# LED_Sch.net
KiCad netlist of a schematic drawn in Altium Designer
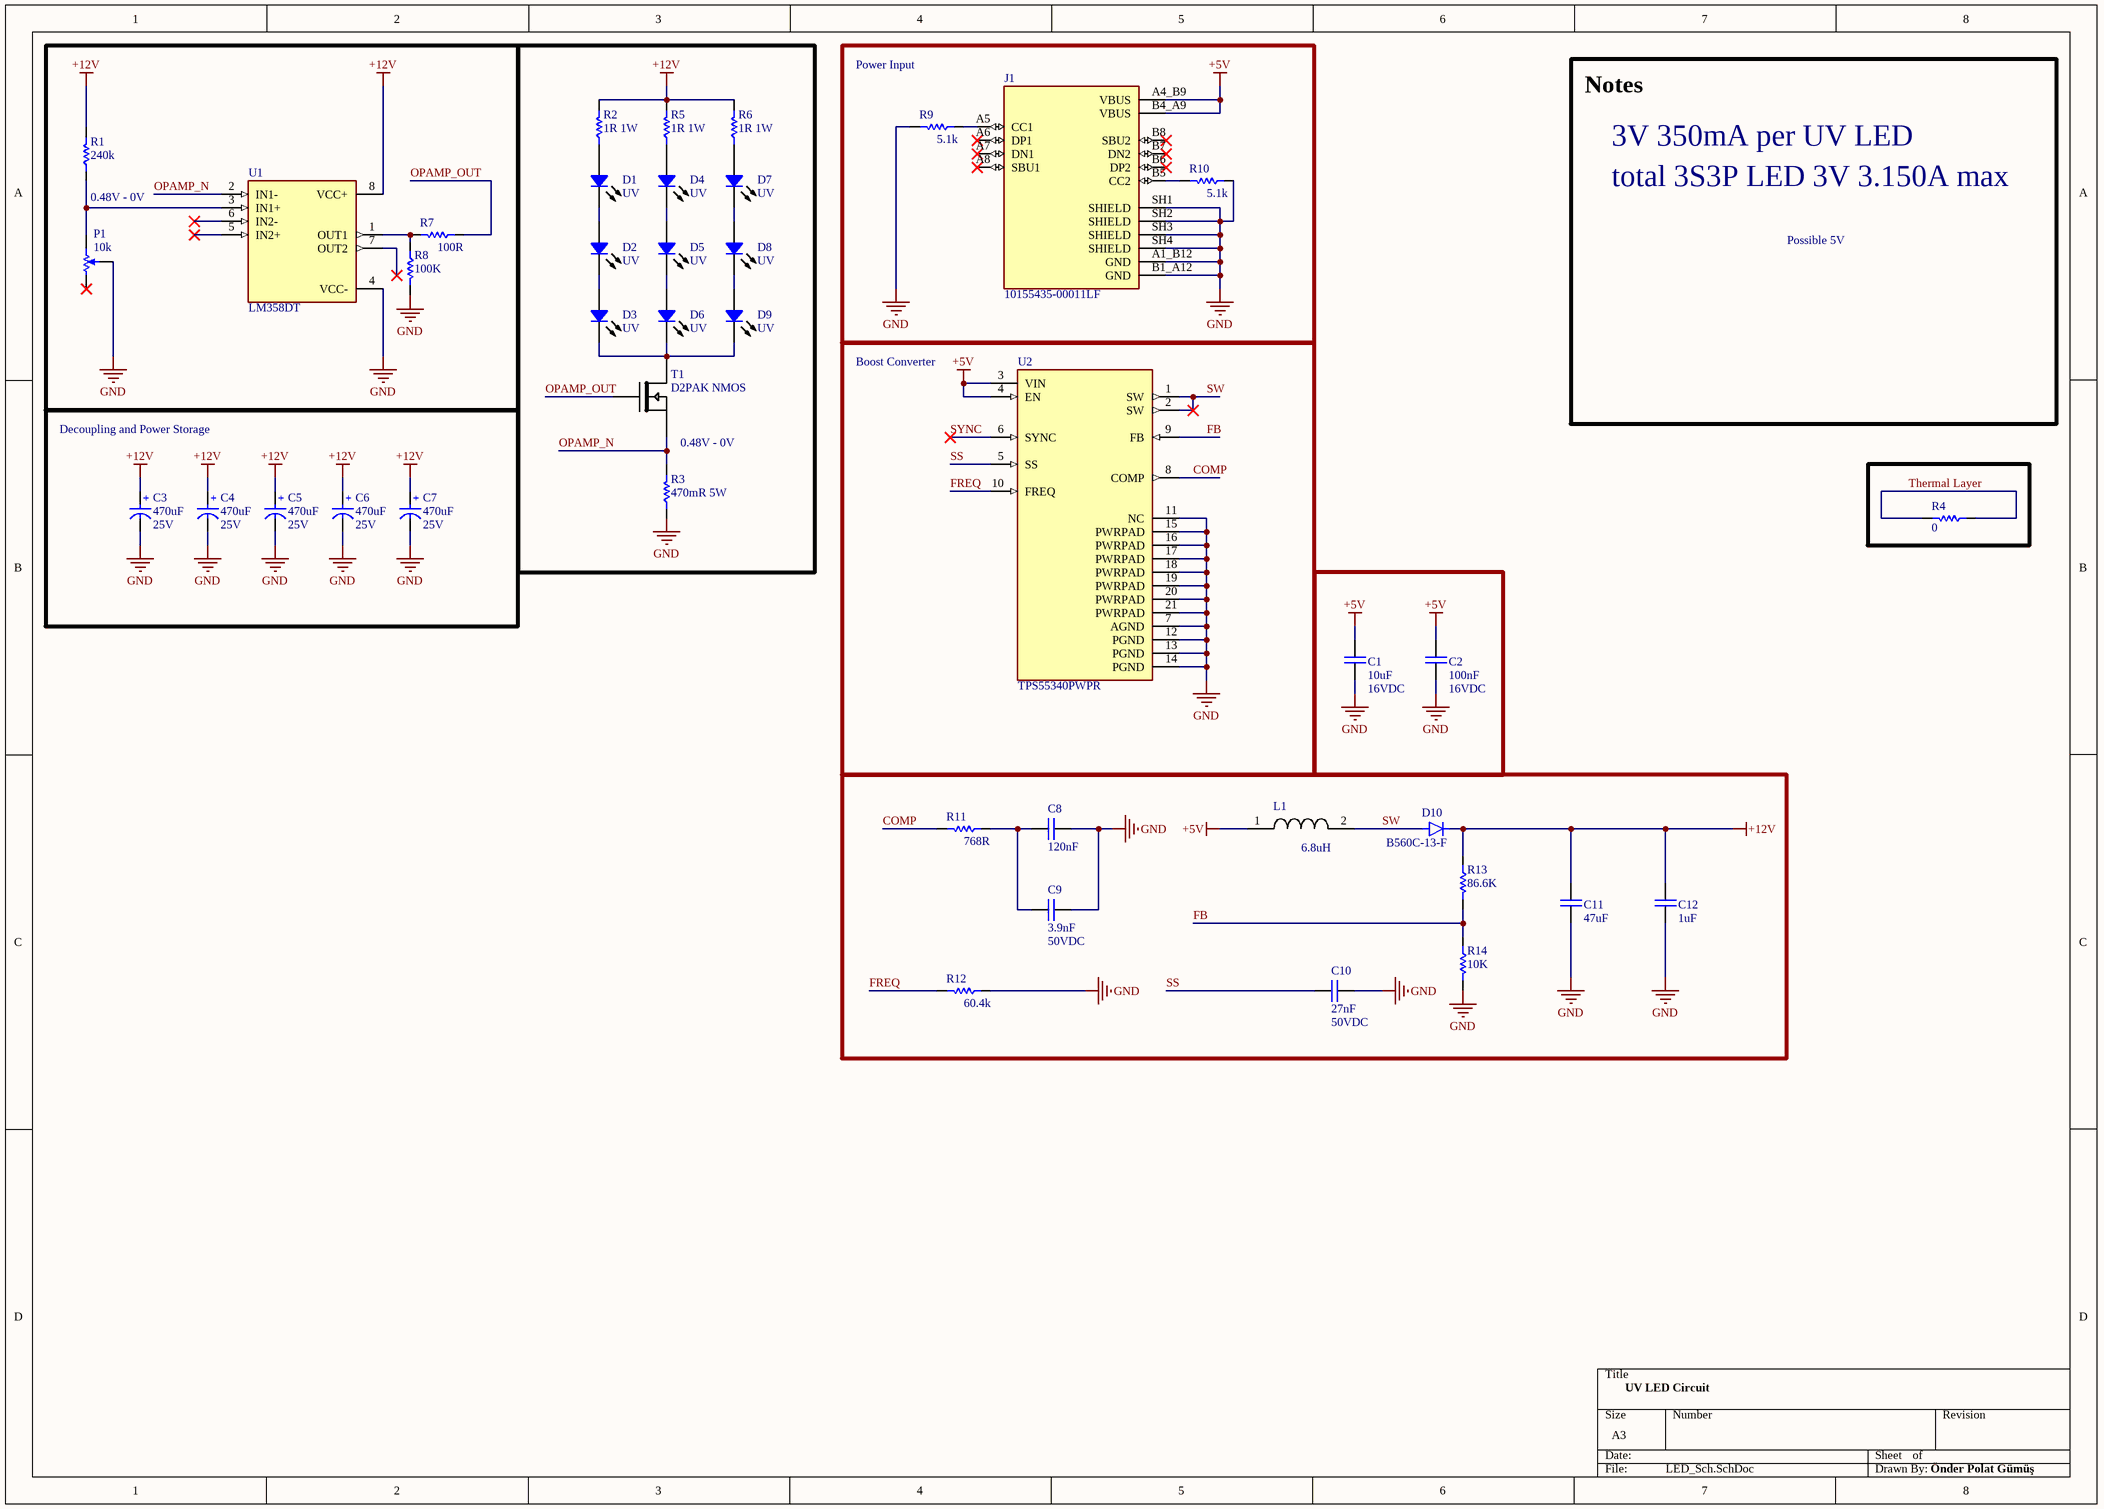
[diagram p0: LED_Sch.SchDoc]

(export (version "E")
  (design (tool "Eeschema 10.0.6"))
  (components
    (comp (ref "C1")
      (value "10uF")
      (footprint "CAP 1206/3216")
      (description "Bipolar ceramic capacitor SMD")
      (fields (field (name "RATING") "16VDC") (field (name "VALIDATION") "Valid"))
      (libsource (lib "aKaReZa") (part "Cap_Multi_SMD"))
    )
    (comp (ref "C2")
      (value "100nF")
      (footprint "CAP 1206/3216")
      (description "Bipolar ceramic capacitor SMD")
      (fields (field (name "RATING") "16VDC") (field (name "VALIDATION") "Valid"))
      (libsource (lib "aKaReZa") (part "Cap_Multi_SMD"))
    )
    (comp (ref "C3")
      (value "470uF")
      (footprint "cap 03")
      (description "Electrolit Capacitor")
      (fields (field (name "RATING") "25V") (field (name "VALIDATION") "Valid"))
      (libsource (lib "aKaReZa") (part "Cap_Electrolit"))
    )
    (comp (ref "C4")
      (value "470uF")
      (footprint "cap 03")
      (description "Electrolit Capacitor")
      (fields (field (name "RATING") "25V") (field (name "VALIDATION") "Valid"))
      (libsource (lib "aKaReZa") (part "Cap_Electrolit"))
    )
    (comp (ref "C5")
      (value "470uF")
      (footprint "cap 03")
      (description "Electrolit Capacitor")
      (fields (field (name "RATING") "25V") (field (name "VALIDATION") "Valid"))
      (libsource (lib "aKaReZa") (part "Cap_Electrolit"))
    )
    (comp (ref "C6")
      (value "470uF")
      (footprint "cap 03")
      (description "Electrolit Capacitor")
      (fields (field (name "RATING") "25V") (field (name "VALIDATION") "Valid"))
      (libsource (lib "aKaReZa") (part "Cap_Electrolit"))
    )
    (comp (ref "C7")
      (value "470uF")
      (footprint "cap 03")
      (description "Electrolit Capacitor")
      (fields (field (name "RATING") "25V") (field (name "VALIDATION") "Valid"))
      (libsource (lib "aKaReZa") (part "Cap_Electrolit"))
    )
    (comp (ref "C8")
      (value "120nF")
      (footprint "1812_C")
      (description "Bipolar ceramic capacitor SMD")
      (fields (field (name "VALIDATION") "Valid"))
      (libsource (lib "aKaReZa") (part "Cap_Multi_SMD"))
    )
    (comp (ref "C9")
      (value "3.9nF")
      (footprint "CAP 0603/1608")
      (description "Bipolar ceramic capacitor SMD")
      (fields (field (name "RATING") "50VDC") (field (name "VALIDATION") "Valid"))
      (libsource (lib "aKaReZa") (part "Cap_Multi_SMD"))
    )
    (comp (ref "C10")
      (value "27nF")
      (footprint "CAP 0805/2012")
      (description "Bipolar ceramic capacitor SMD")
      (fields (field (name "RATING") "50VDC") (field (name "VALIDATION") "Valid"))
      (libsource (lib "aKaReZa") (part "Cap_Multi_SMD"))
    )
    (comp (ref "C11")
      (value "47uF")
      (footprint "CAP 1206/3216")
      (description "Bipolar ceramic capacitor SMD")
      (fields (field (name "VALIDATION") "Valid"))
      (libsource (lib "aKaReZa") (part "Cap_Multi_SMD"))
    )
    (comp (ref "C12")
      (value "1uF")
      (footprint "CAP 1206/3216")
      (description "Bipolar ceramic capacitor SMD")
      (fields (field (name "VALIDATION") "Valid"))
      (libsource (lib "aKaReZa") (part "Cap_Multi_SMD"))
    )
    (comp (ref "D1")
      (value "3'Watt")
      (footprint "POWER LED 1WATT")
      (description "POWER LED SMD")
      (fields (field (name "INFLOW") "UV") (field (name "VALIDATION") "NT"))
      (libsource (lib "aKaReZa") (part "Semi_LED_Power"))
    )
    (comp (ref "D2")
      (value "3'Watt")
      (footprint "POWER LED 1WATT")
      (description "POWER LED SMD")
      (fields (field (name "INFLOW") "UV") (field (name "VALIDATION") "NT"))
      (libsource (lib "aKaReZa") (part "Semi_LED_Power"))
    )
    (comp (ref "D3")
      (value "3'Watt")
      (footprint "POWER LED 1WATT")
      (description "POWER LED SMD")
      (fields (field (name "INFLOW") "UV") (field (name "VALIDATION") "NT"))
      (libsource (lib "aKaReZa") (part "Semi_LED_Power"))
    )
    (comp (ref "D4")
      (value "3'Watt")
      (footprint "POWER LED 1WATT")
      (description "POWER LED SMD")
      (fields (field (name "INFLOW") "UV") (field (name "VALIDATION") "NT"))
      (libsource (lib "aKaReZa") (part "Semi_LED_Power"))
    )
    (comp (ref "D5")
      (value "3'Watt")
      (footprint "POWER LED 1WATT")
      (description "POWER LED SMD")
      (fields (field (name "INFLOW") "UV") (field (name "VALIDATION") "NT"))
      (libsource (lib "aKaReZa") (part "Semi_LED_Power"))
    )
    (comp (ref "D6")
      (value "3'Watt")
      (footprint "POWER LED 1WATT")
      (description "POWER LED SMD")
      (fields (field (name "INFLOW") "UV") (field (name "VALIDATION") "NT"))
      (libsource (lib "aKaReZa") (part "Semi_LED_Power"))
    )
    (comp (ref "D7")
      (value "3'Watt")
      (footprint "POWER LED 1WATT")
      (description "POWER LED SMD")
      (fields (field (name "INFLOW") "UV") (field (name "VALIDATION") "NT"))
      (libsource (lib "aKaReZa") (part "Semi_LED_Power"))
    )
    (comp (ref "D8")
      (value "3'Watt")
      (footprint "POWER LED 1WATT")
      (description "POWER LED SMD")
      (fields (field (name "INFLOW") "UV") (field (name "VALIDATION") "NT"))
      (libsource (lib "aKaReZa") (part "Semi_LED_Power"))
    )
    (comp (ref "D9")
      (value "3'Watt")
      (footprint "POWER LED 1WATT")
      (description "POWER LED SMD")
      (fields (field (name "INFLOW") "UV") (field (name "VALIDATION") "NT"))
      (libsource (lib "aKaReZa") (part "Semi_LED_Power"))
    )
    (comp (ref "D10")
      (value "B560C-13-F")
      (footprint "SMC")
      (description "Diode Schottky 60 V 5A Surface Mount SMC")
      (fields (field (name "MF") "Diodes Inc."))
      (libsource (lib "B560C-13-F") (part "B560C-13-F"))
    )
    (comp (ref "J1")
      (value "10155435-00011LF")
      (footprint "AMPHENOL_10155435-00011LF")
      (libsource (lib "10155435-00011LF") (part "10155435-00011LF"))
    )
    (comp (ref "L1")
      (value "Inductor")
      (footprint "PCBComponent_1")
      (fields (field (name "VALUE?") "6.8uH"))
      (libsource (lib "MSS1260-682ML") (part "Inductor"))
    )
    (comp (ref "P1")
      (value "10k")
      (footprint "POT_WH148")
      (description "Potentiometer")
      (fields (field (name "VALIDATION") "POT 1/8W"))
      (libsource (lib "aKaReZa") (part "Res_Pot"))
    )
    (comp (ref "R1")
      (value "240k")
      (footprint "RES 1206 (3216X08L)")
      (description "Resistor")
      (fields (field (name "VALIDATION") "Valid"))
      (libsource (lib "aKaReZa") (part "Res_SMD"))
    )
    (comp (ref "R2")
      (value "1R")
      (footprint "Axial 1W  7_0mm")
      (description "Resistor")
      (fields (field (name "INFLOW") "1R 1W") (field (name "VALIDATION") "NT"))
      (libsource (lib "aKaReZa") (part "Res_1b_THT_1"))
    )
    (comp (ref "R3")
      (value "27b")
      (footprint "Res 5W")
      (description "Resistor")
      (fields (field (name "INFLOW") "470mR 5W") (field (name "VALIDATION") "NT"))
      (libsource (lib "aKaReZa") (part "Res_27b_THT_5"))
    )
    (comp (ref "R4")
      (value "0")
      (footprint "Res-(1/4)")
      (description "Resistor")
      (fields (field (name "VALIDATION") "Valid"))
      (libsource (lib "aKaReZa") (part "Res_THT"))
    )
    (comp (ref "R5")
      (value "1R")
      (footprint "Axial 1W  7_0mm")
      (description "Resistor")
      (fields (field (name "INFLOW") "1R 1W") (field (name "VALIDATION") "NT"))
      (libsource (lib "aKaReZa") (part "Res_1b_THT_1"))
    )
    (comp (ref "R6")
      (value "1R")
      (footprint "Axial 1W  7_0mm")
      (description "Resistor")
      (fields (field (name "INFLOW") "1R 1W") (field (name "VALIDATION") "NT"))
      (libsource (lib "aKaReZa") (part "Res_1b_THT_1"))
    )
    (comp (ref "R7")
      (value "100R")
      (footprint "RES 1206 (3216X08L)")
      (description "Resistor")
      (fields (field (name "VALIDATION") "Valid"))
      (libsource (lib "aKaReZa") (part "Res_SMD"))
    )
    (comp (ref "R8")
      (value "100K")
      (footprint "RES 1206 (3216X08L)")
      (description "Resistor")
      (fields (field (name "VALIDATION") "Valid"))
      (libsource (lib "aKaReZa") (part "Res_SMD"))
    )
    (comp (ref "R9")
      (value "5.1k")
      (footprint "RES 1206 (3216X08L)")
      (description "Resistor")
      (fields (field (name "VALIDATION") "Valid"))
      (libsource (lib "aKaReZa") (part "Res_SMD"))
    )
    (comp (ref "R10")
      (value "5.1k")
      (footprint "RES 1206 (3216X08L)")
      (description "Resistor")
      (fields (field (name "VALIDATION") "Valid"))
      (libsource (lib "aKaReZa") (part "Res_SMD"))
    )
    (comp (ref "R11")
      (value "768R")
      (footprint "RES 1206 (3216X08L)")
      (description "Resistor")
      (fields (field (name "VALIDATION") "Valid"))
      (libsource (lib "aKaReZa") (part "Res_SMD"))
    )
    (comp (ref "R12")
      (value "60.4k")
      (footprint "RES 1206 (3216X08L)")
      (description "Resistor")
      (fields (field (name "VALIDATION") "Valid"))
      (libsource (lib "aKaReZa") (part "Res_SMD"))
    )
    (comp (ref "R13")
      (value "86.6K")
      (footprint "RES 1206 (3216X08L)")
      (description "Resistor")
      (fields (field (name "VALIDATION") "Valid"))
      (libsource (lib "aKaReZa") (part "Res_SMD"))
    )
    (comp (ref "R14")
      (value "10K")
      (footprint "RES 1206 (3216X08L)")
      (description "Resistor")
      (fields (field (name "VALIDATION") "Valid"))
      (libsource (lib "aKaReZa") (part "Res_SMD"))
    )
    (comp (ref "T1")
      (value "D2PAK NMOS")
      (footprint "D2PAK NMOS")
      (description "for SQM70060EL or any D2PAK NMOS")
      (libsource (lib "D2PAK") (part "D2PAK NMOS"))
    )
    (comp (ref "U1")
      (value "LM358DT")
      (footprint "SOIC127P600X175-8N")
      (description "General Purpose Amplifier 2 Circuit 8-SO")
      (fields (field (name "MF") "STMicroelectronics"))
      (libsource (lib "LM358DT") (part "LM358DT"))
    )
    (comp (ref "U2")
      (value "TPS55340PWPR")
      (footprint "IC_TPS55340PWPR")
      (description "5-A, 40-V, wide VIN boost, flyback, & SEPIC converter")
      (fields (field (name "MF") "Texas Instruments") (field (name "DIGI-KEY_PART_NUMBER") "296-39426-2-ND"))
      (libsource (lib "TPS55340PWPR") (part "TPS55340PWPR"))
    )
  )
  (nets
    (net (code "1") (name "+5V") (class "Default")
      (node (ref "C1") (pin "1") (pinfunction "1_1") (pintype "passive"))
      (node (ref "C2") (pin "1") (pinfunction "1_1") (pintype "passive"))
      (node (ref "J1") (pin "A4_B9") (pinfunction "VBUS_A4_B9") (pintype "power_in"))
      (node (ref "J1") (pin "B4_A9") (pinfunction "VBUS_B4_A9") (pintype "power_in"))
      (node (ref "L1") (pin "1") (pintype "passive"))
      (node (ref "U2") (pin "3") (pinfunction "VIN_3") (pintype "power_in"))
      (node (ref "U2") (pin "4") (pinfunction "EN_4") (pintype "input"))
    )
    (net (code "2") (name "+12V") (class "Default")
      (node (ref "C11") (pin "1") (pinfunction "1_1") (pintype "passive"))
      (node (ref "C12") (pin "1") (pinfunction "1_1") (pintype "passive"))
      (node (ref "C3") (pin "1") (pinfunction "+_1") (pintype "passive"))
      (node (ref "C4") (pin "1") (pinfunction "+_1") (pintype "passive"))
      (node (ref "C5") (pin "1") (pinfunction "+_1") (pintype "passive"))
      (node (ref "C6") (pin "1") (pinfunction "+_1") (pintype "passive"))
      (node (ref "C7") (pin "1") (pinfunction "+_1") (pintype "passive"))
      (node (ref "D10") (pin "C") (pinfunction "C_C") (pintype "passive"))
      (node (ref "R1") (pin "2") (pinfunction "2_2") (pintype "passive"))
      (node (ref "R13") (pin "1") (pinfunction "1_1") (pintype "passive"))
      (node (ref "R2") (pin "2") (pinfunction "2_2") (pintype "passive"))
      (node (ref "R5") (pin "2") (pinfunction "2_2") (pintype "passive"))
      (node (ref "R6") (pin "2") (pinfunction "2_2") (pintype "passive"))
      (node (ref "U1") (pin "8") (pinfunction "VCC+_8") (pintype "power_in"))
    )
    (net (code "3") (name "/COMP") (class "Default")
      (node (ref "R11") (pin "2") (pinfunction "2_2") (pintype "passive"))
      (node (ref "U2") (pin "8") (pinfunction "COMP_8") (pintype "output"))
    )
    (net (code "4") (name "/FB") (class "Default")
      (node (ref "R13") (pin "2") (pinfunction "2_2") (pintype "passive"))
      (node (ref "R14") (pin "1") (pinfunction "1_1") (pintype "passive"))
      (node (ref "U2") (pin "9") (pinfunction "FB_9") (pintype "input"))
    )
    (net (code "5") (name "/FREQ") (class "Default")
      (node (ref "R12") (pin "2") (pinfunction "2_2") (pintype "passive"))
      (node (ref "U2") (pin "10") (pinfunction "FREQ_10") (pintype "input"))
    )
    (net (code "6") (name "/OPAMP_N") (class "Default")
      (node (ref "R3") (pin "2") (pinfunction "2_2") (pintype "passive"))
      (node (ref "T1") (pin "2") (pinfunction "2_2") (pintype "passive"))
      (node (ref "U1") (pin "2") (pinfunction "IN1-_2") (pintype "input"))
    )
    (net (code "7") (name "/OPAMP_OUT") (class "Default")
      (node (ref "R7") (pin "1") (pinfunction "1_1") (pintype "passive"))
      (node (ref "T1") (pin "0") (pinfunction "0_0") (pintype "passive"))
    )
    (net (code "8") (name "/SS") (class "Default")
      (node (ref "C10") (pin "1") (pinfunction "1_1") (pintype "passive"))
      (node (ref "U2") (pin "5") (pinfunction "SS_5") (pintype "input"))
    )
    (net (code "9") (name "/SW") (class "Default")
      (node (ref "D10") (pin "A") (pinfunction "A_A") (pintype "passive"))
      (node (ref "L1") (pin "2") (pintype "passive"))
      (node (ref "U2") (pin "1") (pinfunction "SW_1") (pintype "output"))
      (node (ref "U2") (pin "2") (pinfunction "SW_2") (pintype "output"))
    )
    (net (code "10") (name "/SYNC") (class "Default")
      (node (ref "U2") (pin "6") (pinfunction "SYNC_6") (pintype "input+no_connect"))
    )
    (net (code "11") (name "/Thermal Layer") (class "Default")
      (node (ref "R4") (pin "1") (pinfunction "1_1") (pintype "passive"))
      (node (ref "R4") (pin "2") (pinfunction "2_2") (pintype "passive"))
    )
    (net (code "12") (name "GND") (class "Default")
      (node (ref "C1") (pin "2") (pinfunction "2_2") (pintype "passive"))
      (node (ref "C10") (pin "2") (pinfunction "2_2") (pintype "passive"))
      (node (ref "C11") (pin "2") (pinfunction "2_2") (pintype "passive"))
      (node (ref "C12") (pin "2") (pinfunction "2_2") (pintype "passive"))
      (node (ref "C2") (pin "2") (pinfunction "2_2") (pintype "passive"))
      (node (ref "C3") (pin "2") (pinfunction "-_2") (pintype "passive"))
      (node (ref "C4") (pin "2") (pinfunction "-_2") (pintype "passive"))
      (node (ref "C5") (pin "2") (pinfunction "-_2") (pintype "passive"))
      (node (ref "C6") (pin "2") (pinfunction "-_2") (pintype "passive"))
      (node (ref "C7") (pin "2") (pinfunction "-_2") (pintype "passive"))
      (node (ref "C8") (pin "2") (pinfunction "2_2") (pintype "passive"))
      (node (ref "C9") (pin "2") (pinfunction "2_2") (pintype "passive"))
      (node (ref "J1") (pin "A1_B12") (pinfunction "GND_A1_B12") (pintype "power_in"))
      (node (ref "J1") (pin "B1_A12") (pinfunction "GND_B1_A12") (pintype "power_in"))
      (node (ref "J1") (pin "SH1") (pinfunction "SHIELD_SH1") (pintype "passive"))
      (node (ref "J1") (pin "SH2") (pinfunction "SHIELD_SH2") (pintype "passive"))
      (node (ref "J1") (pin "SH3") (pinfunction "SHIELD_SH3") (pintype "passive"))
      (node (ref "J1") (pin "SH4") (pinfunction "SHIELD_SH4") (pintype "passive"))
      (node (ref "P1") (pin "2") (pinfunction "WIPER_2") (pintype "passive"))
      (node (ref "R10") (pin "1") (pinfunction "1_1") (pintype "passive"))
      (node (ref "R12") (pin "1") (pinfunction "1_1") (pintype "passive"))
      (node (ref "R14") (pin "2") (pinfunction "2_2") (pintype "passive"))
      (node (ref "R3") (pin "1") (pinfunction "1_1") (pintype "passive"))
      (node (ref "R8") (pin "2") (pinfunction "2_2") (pintype "passive"))
      (node (ref "R9") (pin "2") (pinfunction "2_2") (pintype "passive"))
      (node (ref "U1") (pin "4") (pinfunction "VCC-_4") (pintype "power_in"))
      (node (ref "U2") (pin "11") (pinfunction "NC_11") (pintype "power_in"))
      (node (ref "U2") (pin "12") (pinfunction "PGND_12") (pintype "power_in"))
      (node (ref "U2") (pin "13") (pinfunction "PGND_13") (pintype "power_in"))
      (node (ref "U2") (pin "14") (pinfunction "PGND_14") (pintype "power_in"))
      (node (ref "U2") (pin "15") (pinfunction "PWRPAD_15") (pintype "power_in"))
      (node (ref "U2") (pin "16") (pinfunction "PWRPAD_16") (pintype "power_in"))
      (node (ref "U2") (pin "17") (pinfunction "PWRPAD_17") (pintype "power_in"))
      (node (ref "U2") (pin "18") (pinfunction "PWRPAD_18") (pintype "power_in"))
      (node (ref "U2") (pin "19") (pinfunction "PWRPAD_19") (pintype "power_in"))
      (node (ref "U2") (pin "20") (pinfunction "PWRPAD_20") (pintype "power_in"))
      (node (ref "U2") (pin "21") (pinfunction "PWRPAD_21") (pintype "power_in"))
      (node (ref "U2") (pin "7") (pinfunction "AGND_7") (pintype "power_in"))
    )
    (net (code "13") (name "Net-(C8-Pad1)") (class "Default")
      (node (ref "C8") (pin "1") (pinfunction "1_1") (pintype "passive"))
      (node (ref "C9") (pin "1") (pinfunction "1_1") (pintype "passive"))
      (node (ref "R11") (pin "1") (pinfunction "1_1") (pintype "passive"))
    )
    (net (code "14") (name "Net-(D1-Pad1)") (class "Default")
      (node (ref "D1") (pin "1") (pinfunction "1_1") (pintype "passive"))
      (node (ref "R2") (pin "1") (pinfunction "1_1") (pintype "passive"))
    )
    (net (code "15") (name "Net-(D1-Pad2)") (class "Default")
      (node (ref "D1") (pin "2") (pinfunction "2_2") (pintype "passive"))
      (node (ref "D2") (pin "1") (pinfunction "1_1") (pintype "passive"))
    )
    (net (code "16") (name "Net-(D2-Pad2)") (class "Default")
      (node (ref "D2") (pin "2") (pinfunction "2_2") (pintype "passive"))
      (node (ref "D3") (pin "1") (pinfunction "1_1") (pintype "passive"))
    )
    (net (code "17") (name "Net-(D3-Pad2)") (class "Default")
      (node (ref "D3") (pin "2") (pinfunction "2_2") (pintype "passive"))
      (node (ref "D6") (pin "2") (pinfunction "2_2") (pintype "passive"))
      (node (ref "D9") (pin "2") (pinfunction "2_2") (pintype "passive"))
      (node (ref "T1") (pin "1") (pinfunction "1_1") (pintype "passive"))
    )
    (net (code "18") (name "Net-(D4-Pad1)") (class "Default")
      (node (ref "D4") (pin "1") (pinfunction "1_1") (pintype "passive"))
      (node (ref "R5") (pin "1") (pinfunction "1_1") (pintype "passive"))
    )
    (net (code "19") (name "Net-(D4-Pad2)") (class "Default")
      (node (ref "D4") (pin "2") (pinfunction "2_2") (pintype "passive"))
      (node (ref "D5") (pin "1") (pinfunction "1_1") (pintype "passive"))
    )
    (net (code "20") (name "Net-(D5-Pad2)") (class "Default")
      (node (ref "D5") (pin "2") (pinfunction "2_2") (pintype "passive"))
      (node (ref "D6") (pin "1") (pinfunction "1_1") (pintype "passive"))
    )
    (net (code "21") (name "Net-(D7-Pad1)") (class "Default")
      (node (ref "D7") (pin "1") (pinfunction "1_1") (pintype "passive"))
      (node (ref "R6") (pin "1") (pinfunction "1_1") (pintype "passive"))
    )
    (net (code "22") (name "Net-(D7-Pad2)") (class "Default")
      (node (ref "D7") (pin "2") (pinfunction "2_2") (pintype "passive"))
      (node (ref "D8") (pin "1") (pinfunction "1_1") (pintype "passive"))
    )
    (net (code "23") (name "Net-(D8-Pad2)") (class "Default")
      (node (ref "D8") (pin "2") (pinfunction "2_2") (pintype "passive"))
      (node (ref "D9") (pin "1") (pinfunction "1_1") (pintype "passive"))
    )
    (net (code "24") (name "Net-(J1-CC1)") (class "Default")
      (node (ref "J1") (pin "A5") (pinfunction "CC1_A5") (pintype "bidirectional"))
      (node (ref "R9") (pin "1") (pinfunction "1_1") (pintype "passive"))
    )
    (net (code "25") (name "Net-(J1-CC2)") (class "Default")
      (node (ref "J1") (pin "B5") (pinfunction "CC2_B5") (pintype "bidirectional"))
      (node (ref "R10") (pin "2") (pinfunction "2_2") (pintype "passive"))
    )
    (net (code "26") (name "Net-(P1-CCW)") (class "Default")
      (node (ref "P1") (pin "1") (pinfunction "CCW_1") (pintype "passive"))
      (node (ref "R1") (pin "1") (pinfunction "1_1") (pintype "passive"))
      (node (ref "U1") (pin "3") (pinfunction "IN1+_3") (pintype "input"))
    )
    (net (code "27") (name "Net-(U1-OUT1)") (class "Default")
      (node (ref "R7") (pin "2") (pinfunction "2_2") (pintype "passive"))
      (node (ref "R8") (pin "1") (pinfunction "1_1") (pintype "passive"))
      (node (ref "U1") (pin "1") (pinfunction "OUT1_1") (pintype "output"))
    )
    (net (code "28") (name "unconnected-(J1-DN1-PadA7)") (class "Default")
      (node (ref "J1") (pin "A7") (pinfunction "DN1_A7") (pintype "bidirectional+no_connect"))
    )
    (net (code "29") (name "unconnected-(J1-DN2-PadB7)") (class "Default")
      (node (ref "J1") (pin "B7") (pinfunction "DN2_B7") (pintype "bidirectional+no_connect"))
    )
    (net (code "30") (name "unconnected-(J1-DP1-PadA6)") (class "Default")
      (node (ref "J1") (pin "A6") (pinfunction "DP1_A6") (pintype "bidirectional+no_connect"))
    )
    (net (code "31") (name "unconnected-(J1-DP2-PadB6)") (class "Default")
      (node (ref "J1") (pin "B6") (pinfunction "DP2_B6") (pintype "bidirectional+no_connect"))
    )
    (net (code "32") (name "unconnected-(J1-SBU1-PadA8)") (class "Default")
      (node (ref "J1") (pin "A8") (pinfunction "SBU1_A8") (pintype "bidirectional+no_connect"))
    )
    (net (code "33") (name "unconnected-(J1-SBU2-PadB8)") (class "Default")
      (node (ref "J1") (pin "B8") (pinfunction "SBU2_B8") (pintype "bidirectional+no_connect"))
    )
    (net (code "34") (name "unconnected-(P1-CW-Pad3)") (class "Default")
      (node (ref "P1") (pin "3") (pinfunction "CW_3") (pintype "passive+no_connect"))
    )
    (net (code "35") (name "unconnected-(U1-IN2+-Pad5)") (class "Default")
      (node (ref "U1") (pin "5") (pinfunction "IN2+_5") (pintype "input+no_connect"))
    )
    (net (code "36") (name "unconnected-(U1-IN2--Pad6)") (class "Default")
      (node (ref "U1") (pin "6") (pinfunction "IN2-_6") (pintype "input+no_connect"))
    )
    (net (code "37") (name "unconnected-(U1-OUT2-Pad7)") (class "Default")
      (node (ref "U1") (pin "7") (pinfunction "OUT2_7") (pintype "output+no_connect"))
    )
  )
)
